# esp32-s3.net
KiCad netlist of a schematic drawn in Altium Designer
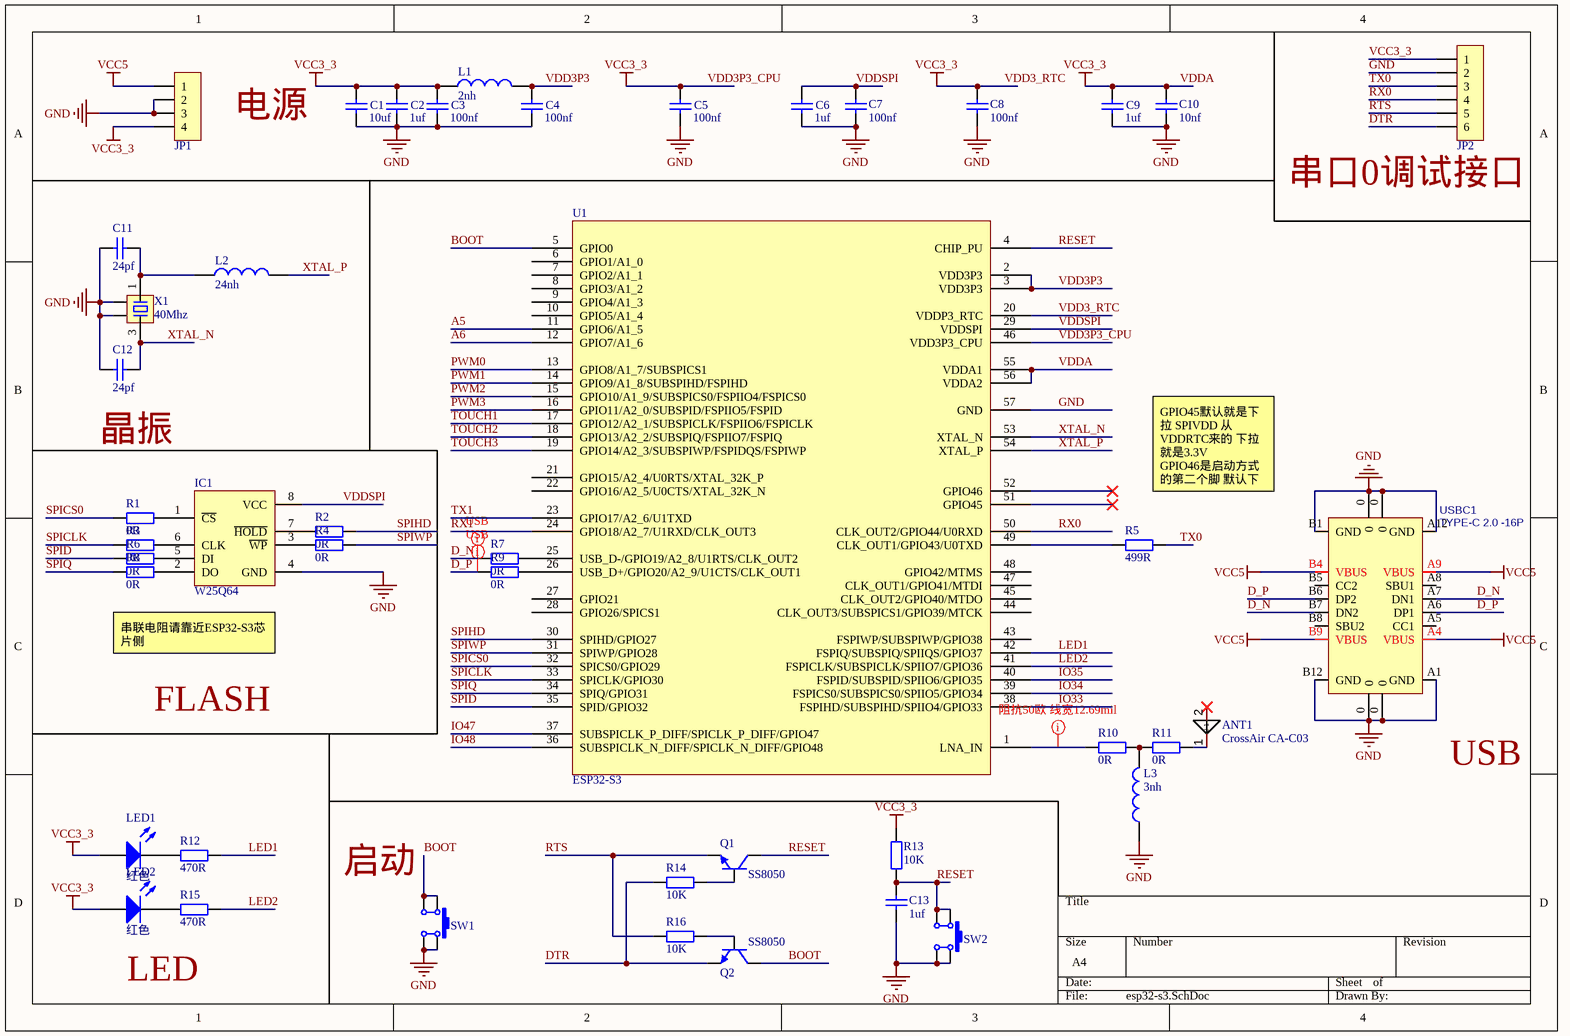
[diagram p0: esp32-s3.SchDoc]

(export (version "E")
  (design (tool "Eeschema 10.0.6"))
  (components
    (comp (ref "ANT1")
      (value "CrossAir CA-C03")
      (footprint "crossair ca-co3")
      (description "2450±50MHz 4.3DBi 50欧 功率3W")
      (fields (field (name "NAME") "CrossAir CA-C03"))
      (libsource (lib "HT") (part "CrossAir CA-C03"))
    )
    (comp (ref "C1")
      (value "10uf")
      (footprint "C0603_L")
      (description "贴片电容/MLCC电容")
      (libsource (lib "0.1 - 电阻-电容-电感-保险丝-晶振-晶体-磁珠-电位器-法拉电容-馈通电容") (part "C"))
    )
    (comp (ref "C2")
      (value "1uf")
      (footprint "C0603_L")
      (description "贴片电容/MLCC电容")
      (libsource (lib "0.1 - 电阻-电容-电感-保险丝-晶振-晶体-磁珠-电位器-法拉电容-馈通电容") (part "C"))
    )
    (comp (ref "C3")
      (value "100nf")
      (footprint "C0402_L")
      (description "贴片电容/MLCC电容")
      (libsource (lib "0.1 - 电阻-电容-电感-保险丝-晶振-晶体-磁珠-电位器-法拉电容-馈通电容") (part "C"))
    )
    (comp (ref "C4")
      (value "100nf")
      (footprint "C0402_L")
      (description "贴片电容/MLCC电容")
      (libsource (lib "0.1 - 电阻-电容-电感-保险丝-晶振-晶体-磁珠-电位器-法拉电容-馈通电容") (part "C"))
    )
    (comp (ref "C5")
      (value "100nf")
      (footprint "C0603_L")
      (description "贴片电容/MLCC电容")
      (libsource (lib "0.1 - 电阻-电容-电感-保险丝-晶振-晶体-磁珠-电位器-法拉电容-馈通电容") (part "C"))
    )
    (comp (ref "C6")
      (value "1uf")
      (footprint "C0603_L")
      (description "贴片电容/MLCC电容")
      (libsource (lib "0.1 - 电阻-电容-电感-保险丝-晶振-晶体-磁珠-电位器-法拉电容-馈通电容") (part "C"))
    )
    (comp (ref "C7")
      (value "100nf")
      (footprint "C0603_L")
      (description "贴片电容/MLCC电容")
      (libsource (lib "0.1 - 电阻-电容-电感-保险丝-晶振-晶体-磁珠-电位器-法拉电容-馈通电容") (part "C"))
    )
    (comp (ref "C8")
      (value "100nf")
      (footprint "C0603_L")
      (description "贴片电容/MLCC电容")
      (libsource (lib "0.1 - 电阻-电容-电感-保险丝-晶振-晶体-磁珠-电位器-法拉电容-馈通电容") (part "C"))
    )
    (comp (ref "C9")
      (value "1uf")
      (footprint "C0603_L")
      (description "贴片电容/MLCC电容")
      (libsource (lib "0.1 - 电阻-电容-电感-保险丝-晶振-晶体-磁珠-电位器-法拉电容-馈通电容") (part "C"))
    )
    (comp (ref "C10")
      (value "10nf")
      (footprint "C0603_L")
      (description "贴片电容/MLCC电容")
      (libsource (lib "0.1 - 电阻-电容-电感-保险丝-晶振-晶体-磁珠-电位器-法拉电容-馈通电容") (part "C"))
    )
    (comp (ref "C11")
      (value "24pf")
      (footprint "C0603_L")
      (description "贴片电容/MLCC电容 C1654")
      (libsource (lib "0.1 - 电阻-电容-电感-保险丝-晶振-晶体-磁珠-电位器-法拉电容-馈通电容") (part "C"))
    )
    (comp (ref "C12")
      (value "24pf")
      (footprint "C0603_L")
      (description "贴片电容/MLCC电容 C1654")
      (libsource (lib "0.1 - 电阻-电容-电感-保险丝-晶振-晶体-磁珠-电位器-法拉电容-馈通电容") (part "C"))
    )
    (comp (ref "C13")
      (value "1uf")
      (footprint "C0603_L")
      (description "贴片电容/MLCC电容")
      (libsource (lib "0.1 - 电阻-电容-电感-保险丝-晶振-晶体-磁珠-电位器-法拉电容-馈通电容") (part "C"))
    )
    (comp (ref "IC1")
      (value "W25Q64")
      (footprint "SOP8W_L")
      (description "SPI Flash C83140")
      (libsource (lib "0.8 - 常见芯片") (part "W25Q"))
    )
    (comp (ref "JP1")
      (value "HDR-1X4")
      (footprint "HDR2.54-LI-4P")
      (description "4P接插件")
      (libsource (lib "5.5 - 2.54mm连接器(KF2EDGK_XH2.54_2.54排针排母)") (part "Header 4"))
    )
    (comp (ref "JP2")
      (value "HDR-1X6")
      (footprint "HDR2.54-LI-6P")
      (description "6P接插件")
      (libsource (lib "5.5 - 2.54mm连接器(KF2EDGK_XH2.54_2.54排针排母)") (part "Header 6"))
    )
    (comp (ref "L1")
      (value "2nh")
      (footprint "L0402")
      (description "贴片小功率电感 C18216")
      (libsource (lib "0.1 - 电阻-电容-电感-保险丝-晶振-晶体-磁珠-电位器-法拉电容-馈通电容") (part "L"))
    )
    (comp (ref "L2")
      (value "24nh")
      (footprint "L0402")
      (description "贴片小功率电感 C74301")
      (libsource (lib "0.1 - 电阻-电容-电感-保险丝-晶振-晶体-磁珠-电位器-法拉电容-馈通电容") (part "L"))
    )
    (comp (ref "L3")
      (value "3nh")
      (footprint "L0402")
      (description "贴片小功率电感")
      (libsource (lib "0.1 - 电阻-电容-电感-保险丝-晶振-晶体-磁珠-电位器-法拉电容-馈通电容") (part "L"))
    )
    (comp (ref "LED1")
      (value "红色")
      (footprint "LED0603_R")
      (description "贴片LED")
      (libsource (lib "0.3 - LED发光二极管-IR二极管_接收管-光耦") (part "LED"))
    )
    (comp (ref "LED2")
      (value "红色")
      (footprint "LED0603_R")
      (description "贴片LED")
      (libsource (lib "0.3 - LED发光二极管-IR二极管_接收管-光耦") (part "LED"))
    )
    (comp (ref "Q1")
      (value "SS8050")
      (footprint "SOT23-3N")
      (description "高频放大-NPN型")
      (libsource (lib "0.4 - 三极管-场效应管-可控硅") (part "8050-SMD"))
    )
    (comp (ref "Q2")
      (value "SS8050")
      (footprint "SOT23-3N")
      (description "高频放大-NPN型")
      (libsource (lib "0.4 - 三极管-场效应管-可控硅") (part "8050-SMD"))
    )
    (comp (ref "R1")
      (value "0R")
      (footprint "R0402_L")
      (description "贴片电阻")
      (libsource (lib "0.1 - 电阻-电容-电感-保险丝-晶振-晶体-磁珠-电位器-法拉电容-馈通电容") (part "R"))
    )
    (comp (ref "R2")
      (value "0R")
      (footprint "R0402_L")
      (description "贴片电阻")
      (libsource (lib "0.1 - 电阻-电容-电感-保险丝-晶振-晶体-磁珠-电位器-法拉电容-馈通电容") (part "R"))
    )
    (comp (ref "R3")
      (value "0R")
      (footprint "R0402_L")
      (description "贴片电阻")
      (libsource (lib "0.1 - 电阻-电容-电感-保险丝-晶振-晶体-磁珠-电位器-法拉电容-馈通电容") (part "R"))
    )
    (comp (ref "R4")
      (value "0R")
      (footprint "R0402_L")
      (description "贴片电阻")
      (libsource (lib "0.1 - 电阻-电容-电感-保险丝-晶振-晶体-磁珠-电位器-法拉电容-馈通电容") (part "R"))
    )
    (comp (ref "R5")
      (value "499R")
      (footprint "R0603_L")
      (description "贴片电阻")
      (libsource (lib "0.1 - 电阻-电容-电感-保险丝-晶振-晶体-磁珠-电位器-法拉电容-馈通电容") (part "R"))
    )
    (comp (ref "R6")
      (value "0R")
      (footprint "R0402_L")
      (description "贴片电阻")
      (libsource (lib "0.1 - 电阻-电容-电感-保险丝-晶振-晶体-磁珠-电位器-法拉电容-馈通电容") (part "R"))
    )
    (comp (ref "R7")
      (value "0R")
      (footprint "R0402_L")
      (description "贴片电阻")
      (libsource (lib "0.1 - 电阻-电容-电感-保险丝-晶振-晶体-磁珠-电位器-法拉电容-馈通电容") (part "R"))
    )
    (comp (ref "R8")
      (value "0R")
      (footprint "R0402_L")
      (description "贴片电阻")
      (libsource (lib "0.1 - 电阻-电容-电感-保险丝-晶振-晶体-磁珠-电位器-法拉电容-馈通电容") (part "R"))
    )
    (comp (ref "R9")
      (value "0R")
      (footprint "R0402_L")
      (description "贴片电阻")
      (libsource (lib "0.1 - 电阻-电容-电感-保险丝-晶振-晶体-磁珠-电位器-法拉电容-馈通电容") (part "R"))
    )
    (comp (ref "R10")
      (value "0R")
      (footprint "R0402_L")
      (description "贴片电阻")
      (libsource (lib "0.1 - 电阻-电容-电感-保险丝-晶振-晶体-磁珠-电位器-法拉电容-馈通电容") (part "R"))
    )
    (comp (ref "R11")
      (value "0R")
      (footprint "R0402_L")
      (description "贴片电阻")
      (libsource (lib "0.1 - 电阻-电容-电感-保险丝-晶振-晶体-磁珠-电位器-法拉电容-馈通电容") (part "R"))
    )
    (comp (ref "R12")
      (value "470R")
      (footprint "R0603_L")
      (description "贴片电阻")
      (libsource (lib "0.1 - 电阻-电容-电感-保险丝-晶振-晶体-磁珠-电位器-法拉电容-馈通电容") (part "R"))
    )
    (comp (ref "R13")
      (value "10K")
      (footprint "R0603_L")
      (description "贴片电阻")
      (libsource (lib "0.1 - 电阻-电容-电感-保险丝-晶振-晶体-磁珠-电位器-法拉电容-馈通电容") (part "R"))
    )
    (comp (ref "R14")
      (value "10K")
      (footprint "R0603_L")
      (description "贴片电阻")
      (libsource (lib "0.1 - 电阻-电容-电感-保险丝-晶振-晶体-磁珠-电位器-法拉电容-馈通电容") (part "R"))
    )
    (comp (ref "R15")
      (value "470R")
      (footprint "R0603_L")
      (description "贴片电阻")
      (libsource (lib "0.1 - 电阻-电容-电感-保险丝-晶振-晶体-磁珠-电位器-法拉电容-馈通电容") (part "R"))
    )
    (comp (ref "R16")
      (value "10K")
      (footprint "R0603_L")
      (description "贴片电阻")
      (libsource (lib "0.1 - 电阻-电容-电感-保险丝-晶振-晶体-磁珠-电位器-法拉电容-馈通电容") (part "R"))
    )
    (comp (ref "SW1")
      (value "3*4*2.5")
      (footprint "SW-SMD-4.2x3.2_4P")
      (description "贴片4脚轻触开关 C2690012")
      (libsource (lib "0.5 - 按键_开关_蜂鸣器_电池_测试点_Mark点_铜柱") (part "SW SMD-3*4*2.5"))
    )
    (comp (ref "SW2")
      (value "3*4*2.5")
      (footprint "SW-SMD-4.2x3.2_4P")
      (description "贴片4脚轻触开关 C2690012")
      (libsource (lib "0.5 - 按键_开关_蜂鸣器_电池_测试点_Mark点_铜柱") (part "SW SMD-3*4*2.5"))
    )
    (comp (ref "U1")
      (value "ESP32-S3")
      (footprint "QFN56 7x7")
      (description "2.4 GHz Wi­Fi + 低功耗蓝牙 SoC")
      (libsource (lib "3.9 - ESP32系列芯片-模组") (part "ESP32-S3"))
    )
    (comp (ref "USBC1")
      (value "TYPE-C 2.0 -16P")
      (footprint "USB-C-SMD_16P")
      (description "USB2.0_Type-C_16Pin母座")
      (libsource (lib "0.6 - 电源_音频_USB Type-C_HDMI_XT60_5557_D-SUB_RJ45_SD-TF_SIM插座") (part "USB2.0_Type-C_16Pin"))
    )
    (comp (ref "X1")
      (value "40Mhz")
      (footprint "XTAL-3225-4P")
      (description "4脚无源晶振(谐振器）C5203551")
      (libsource (lib "0.1 - 电阻-电容-电感-保险丝-晶振-晶体-磁珠-电位器-法拉电容-馈通电容") (part "XTAL-4P"))
    )
  )
  (nets
    (net (code "1") (name "/A5") (class "Default")
      (node (ref "U1") (pin "11") (pinfunction "GPIO6/A1_5_11") (pintype "passive"))
    )
    (net (code "2") (name "/A6") (class "Default")
      (node (ref "U1") (pin "12") (pinfunction "GPIO7/A1_6_12") (pintype "passive"))
    )
    (net (code "3") (name "/BOOT") (class "Default")
      (node (ref "Q2") (pin "3") (pinfunction "C_3") (pintype "passive"))
      (node (ref "SW1") (pin "1") (pinfunction "1_1") (pintype "passive"))
      (node (ref "SW1") (pin "4") (pinfunction "4_4") (pintype "passive"))
      (node (ref "U1") (pin "5") (pinfunction "GPIO0_5") (pintype "passive"))
    )
    (net (code "4") (name "/DTR") (class "Default")
      (node (ref "JP2") (pin "6") (pinfunction "6_6") (pintype "passive"))
      (node (ref "Q2") (pin "2") (pinfunction "E_2") (pintype "passive"))
      (node (ref "R14") (pin "2") (pinfunction "2_2") (pintype "passive"))
    )
    (net (code "5") (name "/D_N") (class "Default")
      (node (ref "R7") (pin "1") (pinfunction "1_1") (pintype "passive"))
      (node (ref "USBC1") (pin "A7") (pinfunction "DN1_A7") (pintype "passive"))
      (node (ref "USBC1") (pin "B7") (pinfunction "DN2_B7") (pintype "passive"))
    )
    (net (code "6") (name "/D_P") (class "Default")
      (node (ref "R9") (pin "1") (pinfunction "1_1") (pintype "passive"))
      (node (ref "USBC1") (pin "A6") (pinfunction "DP1_A6") (pintype "passive"))
      (node (ref "USBC1") (pin "B6") (pinfunction "DP2_B6") (pintype "passive"))
    )
    (net (code "7") (name "/IO33") (class "Default")
      (node (ref "U1") (pin "38") (pinfunction "FSPIHD/SUBSPIHD/SPIIO4/GPIO33_38") (pintype "passive"))
    )
    (net (code "8") (name "/IO34") (class "Default")
      (node (ref "U1") (pin "39") (pinfunction "FSPICS0/SUBSPICS0/SPIIO5/GPIO34_39") (pintype "passive"))
    )
    (net (code "9") (name "/IO35") (class "Default")
      (node (ref "U1") (pin "40") (pinfunction "FSPID/SUBSPID/SPIIO6/GPIO35_40") (pintype "passive"))
    )
    (net (code "10") (name "/IO47") (class "Default")
      (node (ref "U1") (pin "37") (pinfunction "SUBSPICLK_P_DIFF/SPICLK_P_DIFF/GPIO47_37") (pintype "passive"))
    )
    (net (code "11") (name "/IO48") (class "Default")
      (node (ref "U1") (pin "36") (pinfunction "SUBSPICLK_N_DIFF/SPICLK_N_DIFF/GPIO48_36") (pintype "passive"))
    )
    (net (code "12") (name "/LED1") (class "Default")
      (node (ref "R12") (pin "1") (pinfunction "1_1") (pintype "passive"))
      (node (ref "U1") (pin "42") (pinfunction "FSPIQ/SUBSPIQ/SPIIQS/GPIO37_42") (pintype "passive"))
    )
    (net (code "13") (name "/LED2") (class "Default")
      (node (ref "R15") (pin "1") (pinfunction "1_1") (pintype "passive"))
      (node (ref "U1") (pin "41") (pinfunction "FSPICLK/SUBSPICLK/SPIIO7/GPIO36_41") (pintype "passive"))
    )
    (net (code "14") (name "/PWM0") (class "Default")
      (node (ref "U1") (pin "13") (pinfunction "GPIO8/A1_7/SUBSPICS1_13") (pintype "passive"))
    )
    (net (code "15") (name "/PWM1") (class "Default")
      (node (ref "U1") (pin "14") (pinfunction "GPIO9/A1_8/SUBSPIHD/FSPIHD_14") (pintype "passive"))
    )
    (net (code "16") (name "/PWM2") (class "Default")
      (node (ref "U1") (pin "15") (pinfunction "GPIO10/A1_9/SUBSPICS0/FSPIIO4/FSPICS0_15") (pintype "passive"))
    )
    (net (code "17") (name "/PWM3") (class "Default")
      (node (ref "U1") (pin "16") (pinfunction "GPIO11/A2_0/SUBSPID/FSPIIO5/FSPID_16") (pintype "passive"))
    )
    (net (code "18") (name "/RESET") (class "Default")
      (node (ref "C13") (pin "2") (pinfunction "2_2") (pintype "passive"))
      (node (ref "Q1") (pin "3") (pinfunction "C_3") (pintype "passive"))
      (node (ref "R13") (pin "2") (pinfunction "2_2") (pintype "passive"))
      (node (ref "SW2") (pin "1") (pinfunction "1_1") (pintype "passive"))
      (node (ref "SW2") (pin "4") (pinfunction "4_4") (pintype "passive"))
      (node (ref "U1") (pin "4") (pinfunction "CHIP_PU_4") (pintype "passive"))
    )
    (net (code "19") (name "/RTS") (class "Default")
      (node (ref "JP2") (pin "5") (pinfunction "5_5") (pintype "passive"))
      (node (ref "Q1") (pin "2") (pinfunction "E_2") (pintype "passive"))
      (node (ref "R16") (pin "2") (pinfunction "2_2") (pintype "passive"))
    )
    (net (code "20") (name "/RX0") (class "Default")
      (node (ref "JP2") (pin "4") (pinfunction "4_4") (pintype "passive"))
      (node (ref "U1") (pin "50") (pinfunction "CLK_OUT2/GPIO44/U0RXD_50") (pintype "passive"))
    )
    (net (code "21") (name "/RX1") (class "Default")
      (node (ref "U1") (pin "24") (pinfunction "GPIO18/A2_7/U1RXD/CLK_OUT3_24") (pintype "passive"))
    )
    (net (code "22") (name "/SPICLK") (class "Default")
      (node (ref "R3") (pin "1") (pinfunction "1_1") (pintype "passive"))
      (node (ref "U1") (pin "33") (pinfunction "SPICLK/GPIO30_33") (pintype "passive"))
    )
    (net (code "23") (name "/SPICS0") (class "Default")
      (node (ref "R1") (pin "1") (pinfunction "1_1") (pintype "passive"))
      (node (ref "U1") (pin "32") (pinfunction "SPICS0/GPIO29_32") (pintype "passive"))
    )
    (net (code "24") (name "/SPID") (class "Default")
      (node (ref "R6") (pin "1") (pinfunction "1_1") (pintype "passive"))
      (node (ref "U1") (pin "35") (pinfunction "SPID/GPIO32_35") (pintype "passive"))
    )
    (net (code "25") (name "/SPIHD") (class "Default")
      (node (ref "R2") (pin "2") (pinfunction "2_2") (pintype "passive"))
      (node (ref "U1") (pin "30") (pinfunction "SPIHD/GPIO27_30") (pintype "passive"))
    )
    (net (code "26") (name "/SPIQ") (class "Default")
      (node (ref "R8") (pin "1") (pinfunction "1_1") (pintype "passive"))
      (node (ref "U1") (pin "34") (pinfunction "SPIQ/GPIO31_34") (pintype "passive"))
    )
    (net (code "27") (name "/SPIWP") (class "Default")
      (node (ref "R4") (pin "2") (pinfunction "2_2") (pintype "passive"))
      (node (ref "U1") (pin "31") (pinfunction "SPIWP/GPIO28_31") (pintype "passive"))
    )
    (net (code "28") (name "/TOUCH1") (class "Default")
      (node (ref "U1") (pin "17") (pinfunction "GPIO12/A2_1/SUBSPICLK/FSPIIO6/FSPICLK_17") (pintype "passive"))
    )
    (net (code "29") (name "/TOUCH2") (class "Default")
      (node (ref "U1") (pin "18") (pinfunction "GPIO13/A2_2/SUBSPIQ/FSPIIO7/FSPIQ_18") (pintype "passive"))
    )
    (net (code "30") (name "/TOUCH3") (class "Default")
      (node (ref "U1") (pin "19") (pinfunction "GPIO14/A2_3/SUBSPIWP/FSPIDQS/FSPIWP_19") (pintype "passive"))
    )
    (net (code "31") (name "/TX0") (class "Default")
      (node (ref "JP2") (pin "3") (pinfunction "3_3") (pintype "passive"))
      (node (ref "R5") (pin "1") (pinfunction "1_1") (pintype "passive"))
    )
    (net (code "32") (name "/TX1") (class "Default")
      (node (ref "U1") (pin "23") (pinfunction "GPIO17/A2_6/U1TXD_23") (pintype "passive"))
    )
    (net (code "33") (name "/VDD3P3") (class "Default")
      (node (ref "C4") (pin "2") (pinfunction "2_2") (pintype "passive"))
      (node (ref "L1") (pin "2") (pinfunction "2_2") (pintype "passive"))
      (node (ref "U1") (pin "2") (pinfunction "VDD3P3_2") (pintype "passive"))
      (node (ref "U1") (pin "3") (pinfunction "VDD3P3_3") (pintype "passive"))
    )
    (net (code "34") (name "/VDDSPI") (class "Default")
      (node (ref "C6") (pin "2") (pinfunction "2_2") (pintype "passive"))
      (node (ref "C7") (pin "2") (pinfunction "2_2") (pintype "passive"))
      (node (ref "IC1") (pin "8") (pinfunction "VCC_8") (pintype "passive"))
      (node (ref "U1") (pin "29") (pinfunction "VDDSPI_29") (pintype "passive"))
    )
    (net (code "35") (name "/XTAL_N") (class "Default")
      (node (ref "C12") (pin "2") (pinfunction "2_2") (pintype "passive"))
      (node (ref "U1") (pin "53") (pinfunction "XTAL_N_53") (pintype "passive"))
      (node (ref "X1") (pin "3") (pinfunction "3_3") (pintype "passive"))
    )
    (net (code "36") (name "/XTAL_P") (class "Default")
      (node (ref "L2") (pin "2") (pinfunction "2_2") (pintype "passive"))
      (node (ref "U1") (pin "54") (pinfunction "XTAL_P_54") (pintype "passive"))
    )
    (net (code "37") (name "GND") (class "Default")
      (node (ref "C1") (pin "1") (pinfunction "1_1") (pintype "passive"))
      (node (ref "C10") (pin "1") (pinfunction "1_1") (pintype "passive"))
      (node (ref "C11") (pin "1") (pinfunction "1_1") (pintype "passive"))
      (node (ref "C12") (pin "1") (pinfunction "1_1") (pintype "passive"))
      (node (ref "C13") (pin "1") (pinfunction "1_1") (pintype "passive"))
      (node (ref "C2") (pin "1") (pinfunction "1_1") (pintype "passive"))
      (node (ref "C3") (pin "1") (pinfunction "1_1") (pintype "passive"))
      (node (ref "C4") (pin "1") (pinfunction "1_1") (pintype "passive"))
      (node (ref "C5") (pin "1") (pinfunction "1_1") (pintype "passive"))
      (node (ref "C6") (pin "1") (pinfunction "1_1") (pintype "passive"))
      (node (ref "C7") (pin "1") (pinfunction "1_1") (pintype "passive"))
      (node (ref "C8") (pin "1") (pinfunction "1_1") (pintype "passive"))
      (node (ref "C9") (pin "1") (pinfunction "1_1") (pintype "passive"))
      (node (ref "IC1") (pin "4") (pinfunction "GND_4") (pintype "passive"))
      (node (ref "JP1") (pin "2") (pinfunction "2_2") (pintype "passive"))
      (node (ref "JP1") (pin "3") (pinfunction "3_3") (pintype "passive"))
      (node (ref "JP2") (pin "2") (pinfunction "2_2") (pintype "passive"))
      (node (ref "L3") (pin "1") (pinfunction "1_1") (pintype "passive"))
      (node (ref "SW1") (pin "2") (pinfunction "2_2") (pintype "passive"))
      (node (ref "SW1") (pin "3") (pinfunction "3_3") (pintype "passive"))
      (node (ref "SW2") (pin "2") (pinfunction "2_2") (pintype "passive"))
      (node (ref "SW2") (pin "3") (pinfunction "3_3") (pintype "passive"))
      (node (ref "U1") (pin "57") (pinfunction "GND_57") (pintype "passive"))
      (node (ref "USBC1") (pin "0") (pinfunction "0_0") (pintype "passive"))
      (node (ref "USBC1") (pin "A1") (pinfunction "GND_A1") (pintype "passive"))
      (node (ref "USBC1") (pin "A12") (pinfunction "GND_A12") (pintype "passive"))
      (node (ref "USBC1") (pin "B1") (pinfunction "GND_B1") (pintype "passive"))
      (node (ref "USBC1") (pin "B12") (pinfunction "GND_B12") (pintype "passive"))
      (node (ref "X1") (pin "2") (pinfunction "2_2") (pintype "passive"))
      (node (ref "X1") (pin "4") (pinfunction "4_4") (pintype "passive"))
    )
    (net (code "38") (name "Net-(ANT1-Pad1)") (class "Default")
      (node (ref "ANT1") (pin "1") (pinfunction "1_1") (pintype "passive"))
      (node (ref "R11") (pin "2") (pinfunction "2_2") (pintype "passive"))
    )
    (net (code "39") (name "Net-(C11-Pad2)") (class "Default")
      (node (ref "C11") (pin "2") (pinfunction "2_2") (pintype "passive"))
      (node (ref "L2") (pin "1") (pinfunction "1_1") (pintype "passive"))
      (node (ref "X1") (pin "1") (pinfunction "1_1") (pintype "passive"))
    )
    (net (code "40") (name "Net-(IC1-CLK)") (class "Default")
      (node (ref "IC1") (pin "6") (pinfunction "CLK_6") (pintype "passive"))
      (node (ref "R3") (pin "2") (pinfunction "2_2") (pintype "passive"))
    )
    (net (code "41") (name "Net-(IC1-DI)") (class "Default")
      (node (ref "IC1") (pin "5") (pinfunction "DI_5") (pintype "passive"))
      (node (ref "R6") (pin "2") (pinfunction "2_2") (pintype "passive"))
    )
    (net (code "42") (name "Net-(IC1-DO)") (class "Default")
      (node (ref "IC1") (pin "2") (pinfunction "DO_2") (pintype "passive"))
      (node (ref "R8") (pin "2") (pinfunction "2_2") (pintype "passive"))
    )
    (net (code "43") (name "Net-(IC1-~{CS})") (class "Default")
      (node (ref "IC1") (pin "1") (pinfunction "~{CS}_1") (pintype "passive"))
      (node (ref "R1") (pin "2") (pinfunction "2_2") (pintype "passive"))
    )
    (net (code "44") (name "Net-(IC1-~{HOLD})") (class "Default")
      (node (ref "IC1") (pin "7") (pinfunction "~{HOLD}_7") (pintype "passive"))
      (node (ref "R2") (pin "1") (pinfunction "1_1") (pintype "passive"))
    )
    (net (code "45") (name "Net-(IC1-~{WP})") (class "Default")
      (node (ref "IC1") (pin "3") (pinfunction "~{WP}_3") (pintype "passive"))
      (node (ref "R4") (pin "1") (pinfunction "1_1") (pintype "passive"))
    )
    (net (code "46") (name "Net-(L3-Pad2)") (class "Default")
      (node (ref "L3") (pin "2") (pinfunction "2_2") (pintype "passive"))
      (node (ref "R10") (pin "2") (pinfunction "2_2") (pintype "passive"))
      (node (ref "R11") (pin "1") (pinfunction "1_1") (pintype "passive"))
    )
    (net (code "47") (name "Net-(LED1-K)") (class "Default")
      (node (ref "LED1") (pin "2") (pinfunction "K_2") (pintype "passive"))
      (node (ref "R12") (pin "2") (pinfunction "2_2") (pintype "passive"))
    )
    (net (code "48") (name "Net-(LED2-K)") (class "Default")
      (node (ref "LED2") (pin "2") (pinfunction "K_2") (pintype "passive"))
      (node (ref "R15") (pin "2") (pinfunction "2_2") (pintype "passive"))
    )
    (net (code "49") (name "Net-(Q1-B)") (class "Default")
      (node (ref "Q1") (pin "1") (pinfunction "B_1") (pintype "passive"))
      (node (ref "R14") (pin "1") (pinfunction "1_1") (pintype "passive"))
    )
    (net (code "50") (name "Net-(Q2-B)") (class "Default")
      (node (ref "Q2") (pin "1") (pinfunction "B_1") (pintype "passive"))
      (node (ref "R16") (pin "1") (pinfunction "1_1") (pintype "passive"))
    )
    (net (code "51") (name "Net-(U1-CLK_OUT1{slash}GPIO43{slash}U0TXD)") (class "Default")
      (node (ref "R5") (pin "2") (pinfunction "2_2") (pintype "passive"))
      (node (ref "U1") (pin "49") (pinfunction "CLK_OUT1/GPIO43/U0TXD_49") (pintype "passive"))
    )
    (net (code "52") (name "Net-(U1-LNA_IN)") (class "Default")
      (node (ref "R10") (pin "1") (pinfunction "1_1") (pintype "passive"))
      (node (ref "U1") (pin "1") (pinfunction "LNA_IN_1") (pintype "passive"))
    )
    (net (code "53") (name "Net-(U1-USB_D+{slash}GPIO20{slash}A2_9{slash}U1CTS{slash}CLK_OUT1)") (class "Default")
      (node (ref "R9") (pin "2") (pinfunction "2_2") (pintype "passive"))
      (node (ref "U1") (pin "26") (pinfunction "USB_D+/GPIO20/A2_9/U1CTS/CLK_OUT1_26") (pintype "passive"))
    )
    (net (code "54") (name "Net-(U1-USB_D-{slash}GPIO19{slash}A2_8{slash}U1RTS{slash}CLK_OUT2)") (class "Default")
      (node (ref "R7") (pin "2") (pinfunction "2_2") (pintype "passive"))
      (node (ref "U1") (pin "25") (pinfunction "USB_D-/GPIO19/A2_8/U1RTS/CLK_OUT2_25") (pintype "passive"))
    )
    (net (code "55") (name "VCC3_3") (class "Default")
      (node (ref "C1") (pin "2") (pinfunction "2_2") (pintype "passive"))
      (node (ref "C10") (pin "2") (pinfunction "2_2") (pintype "passive"))
      (node (ref "C2") (pin "2") (pinfunction "2_2") (pintype "passive"))
      (node (ref "C3") (pin "2") (pinfunction "2_2") (pintype "passive"))
      (node (ref "C5") (pin "2") (pinfunction "2_2") (pintype "passive"))
      (node (ref "C8") (pin "2") (pinfunction "2_2") (pintype "passive"))
      (node (ref "C9") (pin "2") (pinfunction "2_2") (pintype "passive"))
      (node (ref "JP1") (pin "4") (pinfunction "4_4") (pintype "passive"))
      (node (ref "JP2") (pin "1") (pinfunction "1_1") (pintype "passive"))
      (node (ref "L1") (pin "1") (pinfunction "1_1") (pintype "passive"))
      (node (ref "LED1") (pin "1") (pinfunction "A_1") (pintype "passive"))
      (node (ref "LED2") (pin "1") (pinfunction "A_1") (pintype "passive"))
      (node (ref "R13") (pin "1") (pinfunction "1_1") (pintype "passive"))
      (node (ref "U1") (pin "20") (pinfunction "VDDP3_RTC_20") (pintype "passive"))
      (node (ref "U1") (pin "46") (pinfunction "VDD3P3_CPU_46") (pintype "passive"))
      (node (ref "U1") (pin "55") (pinfunction "VDDA1_55") (pintype "passive"))
      (node (ref "U1") (pin "56") (pinfunction "VDDA2_56") (pintype "passive"))
    )
    (net (code "56") (name "VCC5") (class "Default")
      (node (ref "JP1") (pin "1") (pinfunction "1_1") (pintype "passive"))
      (node (ref "USBC1") (pin "A4") (pinfunction "VBUS_A4") (pintype "passive"))
      (node (ref "USBC1") (pin "A9") (pinfunction "VBUS_A9") (pintype "passive"))
      (node (ref "USBC1") (pin "B4") (pinfunction "VBUS_B4") (pintype "passive"))
      (node (ref "USBC1") (pin "B9") (pinfunction "VBUS_B9") (pintype "passive"))
    )
    (net (code "57") (name "unconnected-(ANT1-Pad2)") (class "Default")
      (node (ref "ANT1") (pin "2") (pinfunction "2_2") (pintype "passive+no_connect"))
    )
    (net (code "58") (name "unconnected-(U1-CLK_OUT1{slash}GPIO41{slash}MTDI-Pad47)") (class "Default")
      (node (ref "U1") (pin "47") (pinfunction "CLK_OUT1/GPIO41/MTDI_47") (pintype "passive"))
    )
    (net (code "59") (name "unconnected-(U1-CLK_OUT2{slash}GPIO40{slash}MTDO-Pad45)") (class "Default")
      (node (ref "U1") (pin "45") (pinfunction "CLK_OUT2/GPIO40/MTDO_45") (pintype "passive"))
    )
    (net (code "60") (name "unconnected-(U1-CLK_OUT3{slash}SUBSPICS1{slash}GPIO39{slash}MTCK-Pad44)") (class "Default")
      (node (ref "U1") (pin "44") (pinfunction "CLK_OUT3/SUBSPICS1/GPIO39/MTCK_44") (pintype "passive"))
    )
    (net (code "61") (name "unconnected-(U1-FSPIWP{slash}SUBSPIWP{slash}GPIO38-Pad43)") (class "Default")
      (node (ref "U1") (pin "43") (pinfunction "FSPIWP/SUBSPIWP/GPIO38_43") (pintype "passive"))
    )
    (net (code "62") (name "unconnected-(U1-GPIO1{slash}A1_0-Pad6)") (class "Default")
      (node (ref "U1") (pin "6") (pinfunction "GPIO1/A1_0_6") (pintype "passive"))
    )
    (net (code "63") (name "unconnected-(U1-GPIO2{slash}A1_1-Pad7)") (class "Default")
      (node (ref "U1") (pin "7") (pinfunction "GPIO2/A1_1_7") (pintype "passive"))
    )
    (net (code "64") (name "unconnected-(U1-GPIO3{slash}A1_2-Pad8)") (class "Default")
      (node (ref "U1") (pin "8") (pinfunction "GPIO3/A1_2_8") (pintype "passive"))
    )
    (net (code "65") (name "unconnected-(U1-GPIO4{slash}A1_3-Pad9)") (class "Default")
      (node (ref "U1") (pin "9") (pinfunction "GPIO4/A1_3_9") (pintype "passive"))
    )
    (net (code "66") (name "unconnected-(U1-GPIO5{slash}A1_4-Pad10)") (class "Default")
      (node (ref "U1") (pin "10") (pinfunction "GPIO5/A1_4_10") (pintype "passive"))
    )
    (net (code "67") (name "unconnected-(U1-GPIO15{slash}A2_4{slash}U0RTS{slash}XTAL_32K_P-Pad21)") (class "Default")
      (node (ref "U1") (pin "21") (pinfunction "GPIO15/A2_4/U0RTS/XTAL_32K_P_21") (pintype "passive"))
    )
    (net (code "68") (name "unconnected-(U1-GPIO16{slash}A2_5{slash}U0CTS{slash}XTAL_32K_N-Pad22)") (class "Default")
      (node (ref "U1") (pin "22") (pinfunction "GPIO16/A2_5/U0CTS/XTAL_32K_N_22") (pintype "passive"))
    )
    (net (code "69") (name "unconnected-(U1-GPIO21-Pad27)") (class "Default")
      (node (ref "U1") (pin "27") (pinfunction "GPIO21_27") (pintype "passive"))
    )
    (net (code "70") (name "unconnected-(U1-GPIO26{slash}SPICS1-Pad28)") (class "Default")
      (node (ref "U1") (pin "28") (pinfunction "GPIO26/SPICS1_28") (pintype "passive"))
    )
    (net (code "71") (name "unconnected-(U1-GPIO42{slash}MTMS-Pad48)") (class "Default")
      (node (ref "U1") (pin "48") (pinfunction "GPIO42/MTMS_48") (pintype "passive"))
    )
    (net (code "72") (name "unconnected-(U1-GPIO45-Pad51)") (class "Default")
      (node (ref "U1") (pin "51") (pinfunction "GPIO45_51") (pintype "passive+no_connect"))
    )
    (net (code "73") (name "unconnected-(U1-GPIO46-Pad52)") (class "Default")
      (node (ref "U1") (pin "52") (pinfunction "GPIO46_52") (pintype "passive+no_connect"))
    )
    (net (code "74") (name "unconnected-(USBC1-CC1-PadA5)") (class "Default")
      (node (ref "USBC1") (pin "A5") (pinfunction "CC1_A5") (pintype "passive"))
    )
    (net (code "75") (name "unconnected-(USBC1-CC2-PadB5)") (class "Default")
      (node (ref "USBC1") (pin "B5") (pinfunction "CC2_B5") (pintype "passive"))
    )
    (net (code "76") (name "unconnected-(USBC1-SBU1-PadA8)") (class "Default")
      (node (ref "USBC1") (pin "A8") (pinfunction "SBU1_A8") (pintype "passive"))
    )
    (net (code "77") (name "unconnected-(USBC1-SBU2-PadB8)") (class "Default")
      (node (ref "USBC1") (pin "B8") (pinfunction "SBU2_B8") (pintype "passive"))
    )
  )
)
